# lora1262m.net
KiCad netlist of a schematic drawn in Altium Designer
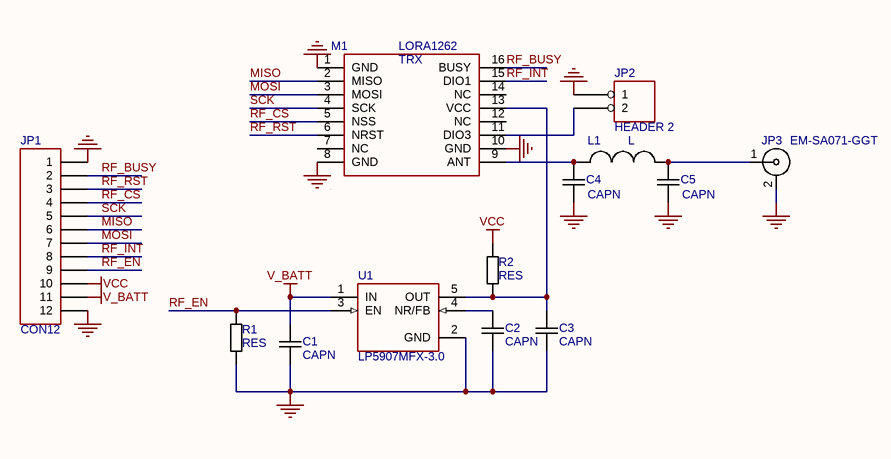
[diagram p0: lora1262m.SchDoc]

(export (version "E")
  (design (tool "Eeschema 10.0.6"))
  (components
    (comp (ref "C1")
      (value "CAPN")
      (footprint "C-0805")
      (fields (field (name "VOLTAGE") "50V"))
      (libsource (lib "Passive") (part "CAPN"))
    )
    (comp (ref "C2")
      (value "CAPN")
      (footprint "C-0603")
      (fields (field (name "VOLTAGE") "50V"))
      (libsource (lib "Passive") (part "CAPN"))
    )
    (comp (ref "C3")
      (value "CAPN")
      (footprint "C-0805")
      (fields (field (name "VOLTAGE") "50V"))
      (libsource (lib "Passive") (part "CAPN"))
    )
    (comp (ref "C4")
      (value "CAPN")
      (footprint "C-0603")
      (fields (field (name "VOLTAGE") "50V"))
      (libsource (lib "Passive") (part "CAPN"))
    )
    (comp (ref "C5")
      (value "CAPN")
      (footprint "C-0603")
      (fields (field (name "VOLTAGE") "50V"))
      (libsource (lib "Passive") (part "CAPN"))
    )
    (comp (ref "JP1")
      (value "CON12")
      (footprint "PBS1-12R")
      (description "Connector")
      (libsource (lib "Connectors") (part "CON12"))
    )
    (comp (ref "JP2")
      (value "HEADER 2")
      (footprint "PLS1-2")
      (libsource (lib "Connectors") (part "HEADER 2"))
    )
    (comp (ref "JP3")
      (value "EM-SA071-GGT")
      (footprint "SMA_F_EDGE")
      (description "SMA Female R/A PCB Mount")
      (libsource (lib "Connectors") (part "SMA"))
    )
    (comp (ref "L1") (value "L") (footprint "L-0603") (libsource (lib "Passive") (part "L")))
    (comp (ref "M1")
      (value "LORA1262")
      (footprint "LGA16_LORA1280")
      (libsource (lib "RFmodules") (part "LORA1262"))
    )
    (comp (ref "R1") (value "RES") (footprint "R-0603") (libsource (lib "Passive") (part "RES")))
    (comp (ref "R2") (value "RES") (footprint "R-0603") (libsource (lib "Passive") (part "RES")))
    (comp (ref "U1")
      (value "LP5907MFX-3.0")
      (footprint "SOT-23-5")
      (description "250mA Low-Dropout Regulator")
      (libsource (lib "ICs") (part "LP5907"))
    )
  )
  (nets
    (net (code "1") (name "/MISO") (class "Default")
      (node (ref "JP1") (pin "6") (pinfunction "6_6") (pintype "passive"))
      (node (ref "M1") (pin "2") (pinfunction "MISO_2") (pintype "passive"))
    )
    (net (code "2") (name "/MOSI") (class "Default")
      (node (ref "JP1") (pin "7") (pinfunction "7_7") (pintype "passive"))
      (node (ref "M1") (pin "3") (pinfunction "MOSI_3") (pintype "passive"))
    )
    (net (code "3") (name "/RF_BUSY") (class "Default")
      (node (ref "JP1") (pin "2") (pinfunction "2_2") (pintype "passive"))
      (node (ref "M1") (pin "16") (pinfunction "BUSY_16") (pintype "passive"))
    )
    (net (code "4") (name "/RF_CS") (class "Default")
      (node (ref "JP1") (pin "4") (pinfunction "4_4") (pintype "passive"))
      (node (ref "M1") (pin "5") (pinfunction "NSS_5") (pintype "passive"))
    )
    (net (code "5") (name "/RF_EN") (class "Default")
      (node (ref "JP1") (pin "9") (pinfunction "9_9") (pintype "passive"))
      (node (ref "R1") (pin "2") (pinfunction "2_2") (pintype "passive"))
      (node (ref "U1") (pin "3") (pinfunction "EN_3") (pintype "input"))
    )
    (net (code "6") (name "/RF_INT") (class "Default")
      (node (ref "JP1") (pin "8") (pinfunction "8_8") (pintype "passive"))
      (node (ref "M1") (pin "15") (pinfunction "DIO1_15") (pintype "passive"))
    )
    (net (code "7") (name "/RF_RST") (class "Default")
      (node (ref "JP1") (pin "3") (pinfunction "3_3") (pintype "passive"))
      (node (ref "M1") (pin "6") (pinfunction "NRST_6") (pintype "passive"))
    )
    (net (code "8") (name "/SCK") (class "Default")
      (node (ref "JP1") (pin "5") (pinfunction "5_5") (pintype "passive"))
      (node (ref "M1") (pin "4") (pinfunction "SCK_4") (pintype "passive"))
    )
    (net (code "9") (name "GND") (class "Default")
      (node (ref "C1") (pin "2") (pinfunction "2_2") (pintype "passive"))
      (node (ref "C2") (pin "2") (pinfunction "2_2") (pintype "passive"))
      (node (ref "C3") (pin "2") (pinfunction "2_2") (pintype "passive"))
      (node (ref "C4") (pin "2") (pinfunction "2_2") (pintype "passive"))
      (node (ref "C5") (pin "2") (pinfunction "2_2") (pintype "passive"))
      (node (ref "JP1") (pin "1") (pinfunction "1_1") (pintype "passive"))
      (node (ref "JP1") (pin "12") (pinfunction "12_12") (pintype "passive"))
      (node (ref "JP2") (pin "1") (pinfunction "1_1") (pintype "passive"))
      (node (ref "JP3") (pin "2") (pinfunction "2_2") (pintype "passive"))
      (node (ref "M1") (pin "1") (pinfunction "GND_1") (pintype "passive"))
      (node (ref "M1") (pin "10") (pinfunction "GND_10") (pintype "passive"))
      (node (ref "M1") (pin "8") (pinfunction "GND_8") (pintype "passive"))
      (node (ref "R1") (pin "1") (pinfunction "1_1") (pintype "passive"))
      (node (ref "U1") (pin "2") (pinfunction "GND_2") (pintype "power_in"))
    )
    (net (code "10") (name "Net-(C5-Pad1)") (class "Default")
      (node (ref "C5") (pin "1") (pinfunction "1_1") (pintype "passive"))
      (node (ref "JP3") (pin "1") (pinfunction "1_1") (pintype "passive"))
      (node (ref "L1") (pin "2") (pinfunction "2_2") (pintype "passive"))
    )
    (net (code "11") (name "Net-(M1-ANT)") (class "Default")
      (node (ref "C4") (pin "1") (pinfunction "1_1") (pintype "passive"))
      (node (ref "L1") (pin "1") (pinfunction "1_1") (pintype "passive"))
      (node (ref "M1") (pin "9") (pinfunction "ANT_9") (pintype "passive"))
    )
    (net (code "12") (name "Net-(M1-DIO3)") (class "Default")
      (node (ref "JP2") (pin "2") (pinfunction "2_2") (pintype "passive"))
      (node (ref "M1") (pin "11") (pinfunction "DIO3_11") (pintype "passive"))
    )
    (net (code "13") (name "Net-(M1-VCC)") (class "Default")
      (node (ref "C3") (pin "1") (pinfunction "1_1") (pintype "passive"))
      (node (ref "M1") (pin "13") (pinfunction "VCC_13") (pintype "passive"))
      (node (ref "R2") (pin "1") (pinfunction "1_1") (pintype "passive"))
      (node (ref "U1") (pin "5") (pinfunction "OUT_5") (pintype "power_in"))
    )
    (net (code "14") (name "Net-(U1-NR{slash}FB)") (class "Default")
      (node (ref "C2") (pin "1") (pinfunction "1_1") (pintype "passive"))
      (node (ref "U1") (pin "4") (pinfunction "NR/FB_4") (pintype "input"))
    )
    (net (code "15") (name "VCC") (class "Default")
      (node (ref "JP1") (pin "10") (pinfunction "10_10") (pintype "passive"))
      (node (ref "R2") (pin "2") (pinfunction "2_2") (pintype "passive"))
    )
    (net (code "16") (name "V_BATT") (class "Default")
      (node (ref "C1") (pin "1") (pinfunction "1_1") (pintype "passive"))
      (node (ref "JP1") (pin "11") (pinfunction "11_11") (pintype "passive"))
      (node (ref "U1") (pin "1") (pinfunction "IN_1") (pintype "power_in"))
    )
    (net (code "17") (name "unconnected-(M1-NC-Pad7)") (class "Default")
      (node (ref "M1") (pin "7") (pinfunction "NC_7") (pintype "passive"))
    )
    (net (code "18") (name "unconnected-(M1-NC-Pad12)") (class "Default")
      (node (ref "M1") (pin "12") (pinfunction "NC_12") (pintype "passive"))
    )
    (net (code "19") (name "unconnected-(M1-NC-Pad14)") (class "Default")
      (node (ref "M1") (pin "14") (pinfunction "NC_14") (pintype "passive"))
    )
  )
)
